# grintch_pcb.net
KiCad netlist of a schematic drawn in EAGLE
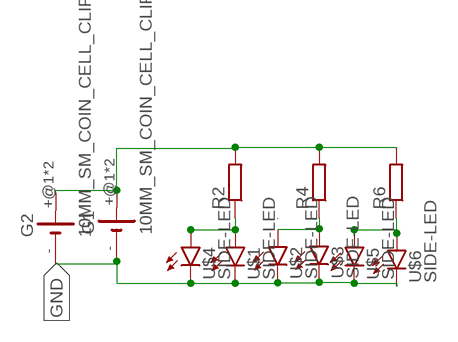
[diagram p0: schematic, sheet 1]

(export (version "E")
  (design (tool "Eeschema 10.0.6"))
  (components
    (comp (ref "G1")
      (value "10MM_SM_COIN_CELL_CLIP")
      (footprint "eagle-import:10MM_SM_COIN_CELL_CLIP")
      (libsource (lib "eagle-import") (part "10MM_SM_COIN_CELL_CLIP"))
    )
    (comp (ref "G2")
      (value "10MM_SM_COIN_CELL_CLIP")
      (footprint "eagle-import:10MM_SM_COIN_CELL_CLIP")
      (libsource (lib "eagle-import") (part "10MM_SM_COIN_CELL_CLIP"))
    )
    (comp (ref "R2")
      (value "R-EU_R0805")
      (footprint "eagle-import:R0805")
      (libsource (lib "eagle-import") (part "R-EU_R0805"))
    )
    (comp (ref "R4")
      (value "R-EU_R0805")
      (footprint "eagle-import:R0805")
      (libsource (lib "eagle-import") (part "R-EU_R0805"))
    )
    (comp (ref "R6")
      (value "R-EU_R0805")
      (footprint "eagle-import:R0805")
      (libsource (lib "eagle-import") (part "R-EU_R0805"))
    )
    (comp (ref "U$1")
      (value "SIDE-LED")
      (footprint "eagle-import:SIDE-LED")
      (libsource (lib "eagle-import") (part "SIDE-LED"))
    )
    (comp (ref "U$2")
      (value "SIDE-LED")
      (footprint "eagle-import:SIDE-LED")
      (libsource (lib "eagle-import") (part "SIDE-LED"))
    )
    (comp (ref "U$3")
      (value "SIDE-LED")
      (footprint "eagle-import:SIDE-LED")
      (libsource (lib "eagle-import") (part "SIDE-LED"))
    )
    (comp (ref "U$4")
      (value "SIDE-LED")
      (footprint "eagle-import:SIDE-LED")
      (libsource (lib "eagle-import") (part "SIDE-LED"))
    )
    (comp (ref "U$5")
      (value "SIDE-LED")
      (footprint "eagle-import:SIDE-LED")
      (libsource (lib "eagle-import") (part "SIDE-LED"))
    )
    (comp (ref "U$6")
      (value "SIDE-LED")
      (footprint "eagle-import:SIDE-LED")
      (libsource (lib "eagle-import") (part "SIDE-LED"))
    )
  )
  (nets
    (net (code "1") (name "GND") (class "Default")
      (node (ref "G1") (pin "-") (pinfunction "-_-") (pintype "passive"))
      (node (ref "G2") (pin "-") (pinfunction "-_-") (pintype "passive"))
      (node (ref "U$1") (pin "P$2") (pinfunction "C_P$2") (pintype "passive"))
      (node (ref "U$2") (pin "P$2") (pinfunction "C_P$2") (pintype "passive"))
      (node (ref "U$3") (pin "P$2") (pinfunction "C_P$2") (pintype "passive"))
      (node (ref "U$4") (pin "P$2") (pinfunction "C_P$2") (pintype "passive"))
      (node (ref "U$5") (pin "P$2") (pinfunction "C_P$2") (pintype "passive"))
      (node (ref "U$6") (pin "P$2") (pinfunction "C_P$2") (pintype "passive"))
    )
    (net (code "2") (name "Net-(G1-+-Pad+@1)") (class "Default")
      (node (ref "G1") (pin "+@1") (pinfunction "+_+@1") (pintype "passive"))
      (node (ref "G1") (pin "+@2") (pinfunction "+_+@2") (pintype "passive"))
      (node (ref "G2") (pin "+@1") (pinfunction "+_+@1") (pintype "passive"))
      (node (ref "G2") (pin "+@2") (pinfunction "+_+@2") (pintype "passive"))
      (node (ref "R2") (pin "2") (pinfunction "2_2") (pintype "passive"))
      (node (ref "R4") (pin "2") (pinfunction "2_2") (pintype "passive"))
      (node (ref "R6") (pin "2") (pinfunction "2_2") (pintype "passive"))
    )
    (net (code "3") (name "Net-(U$1-A)") (class "Default")
      (node (ref "R2") (pin "1") (pinfunction "1_1") (pintype "passive"))
      (node (ref "U$1") (pin "P$1") (pinfunction "A_P$1") (pintype "passive"))
      (node (ref "U$4") (pin "P$1") (pinfunction "A_P$1") (pintype "passive"))
    )
    (net (code "4") (name "Net-(U$2-A)") (class "Default")
      (node (ref "R4") (pin "1") (pinfunction "1_1") (pintype "passive"))
      (node (ref "U$2") (pin "P$1") (pinfunction "A_P$1") (pintype "passive"))
      (node (ref "U$3") (pin "P$1") (pinfunction "A_P$1") (pintype "passive"))
    )
    (net (code "5") (name "Net-(U$5-A)") (class "Default")
      (node (ref "R6") (pin "1") (pinfunction "1_1") (pintype "passive"))
      (node (ref "U$5") (pin "P$1") (pinfunction "A_P$1") (pintype "passive"))
      (node (ref "U$6") (pin "P$1") (pinfunction "A_P$1") (pintype "passive"))
    )
  )
)
